# Step_Down.net
KiCad netlist of a schematic drawn in Altium Designer
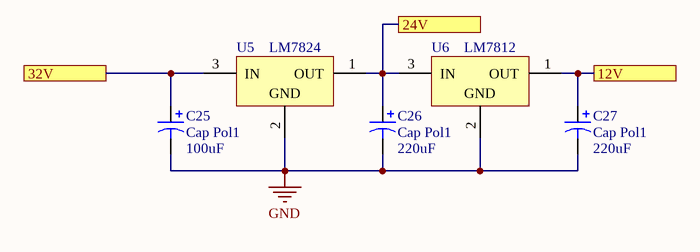
[diagram p0: Step Down.SchDoc]

(export (version "E")
  (design (tool "Eeschema 10.0.6"))
  (components
    (comp (ref "C25")
      (value "Cap Pol1")
      (footprint "CAPR D250 H450 R100 mil")
      (description "Polarized Capacitor (Radial)")
      (fields (field (name "ALTIUM_VALUE") "100uF") (field (name "PUBLISHER") "Altium Limited"))
      (libsource (lib "Miscellaneous Devices") (part "Cap Pol1"))
    )
    (comp (ref "C26")
      (value "Cap Pol1")
      (footprint "CAPR D400 H500 R200 mil")
      (description "Polarized Capacitor (Radial)")
      (fields (field (name "ALTIUM_VALUE") "220uF") (field (name "PUBLISHER") "Altium Limited"))
      (libsource (lib "Miscellaneous Devices") (part "Cap Pol1"))
    )
    (comp (ref "C27")
      (value "Cap Pol1")
      (footprint "CAPR D250 H450 R100 mil")
      (description "Polarized Capacitor (Radial)")
      (fields (field (name "ALTIUM_VALUE") "220uF") (field (name "PUBLISHER") "Altium Limited"))
      (libsource (lib "Miscellaneous Devices") (part "Cap Pol1"))
    )
    (comp (ref "U5")
      (value "LM7824")
      (footprint "TO-220_B")
      (description "3-Terminal Positive Regulators, 3-pin TO-92")
      (fields
        (field (name "PARTNUMBER") "LM78L12ACZ")
        (field (name "MANUFACTURER") "National Semiconductor")
        (field (name "PUBLISHER") "Altium Limited")
      )
      (libsource (lib "NSC LDO") (part "LM78L12ACZ"))
    )
    (comp (ref "U6")
      (value "LM7812")
      (footprint "TO-220_B")
      (description "3-Terminal Positive Regulators, 3-pin TO-92")
      (fields
        (field (name "PARTNUMBER") "LM78L12ACZ")
        (field (name "MANUFACTURER") "National Semiconductor")
        (field (name "PUBLISHER") "Altium Limited")
      )
      (libsource (lib "NSC LDO") (part "LM78L12ACZ"))
    )
  )
  (nets
    (net (code "1") (name "/12V") (class "Default")
      (node (ref "C27") (pin "1") (pinfunction "1_1") (pintype "passive"))
      (node (ref "U6") (pin "1") (pinfunction "OUT_1") (pintype "power_in"))
    )
    (net (code "2") (name "/24V") (class "Default")
      (node (ref "C26") (pin "1") (pinfunction "1_1") (pintype "passive"))
      (node (ref "U5") (pin "1") (pinfunction "OUT_1") (pintype "power_in"))
      (node (ref "U6") (pin "3") (pinfunction "IN_3") (pintype "power_in"))
    )
    (net (code "3") (name "/32V") (class "Default")
      (node (ref "C25") (pin "1") (pinfunction "1_1") (pintype "passive"))
      (node (ref "U5") (pin "3") (pinfunction "IN_3") (pintype "power_in"))
    )
    (net (code "4") (name "GND") (class "Default")
      (node (ref "C25") (pin "2") (pinfunction "2_2") (pintype "passive"))
      (node (ref "C26") (pin "2") (pinfunction "2_2") (pintype "passive"))
      (node (ref "C27") (pin "2") (pinfunction "2_2") (pintype "passive"))
      (node (ref "U5") (pin "2") (pinfunction "GND_2") (pintype "power_in"))
      (node (ref "U6") (pin "2") (pinfunction "GND_2") (pintype "power_in"))
    )
  )
)
